# Equipo04_EsquematicoLab05.net
KiCad netlist of a schematic drawn in EAGLE
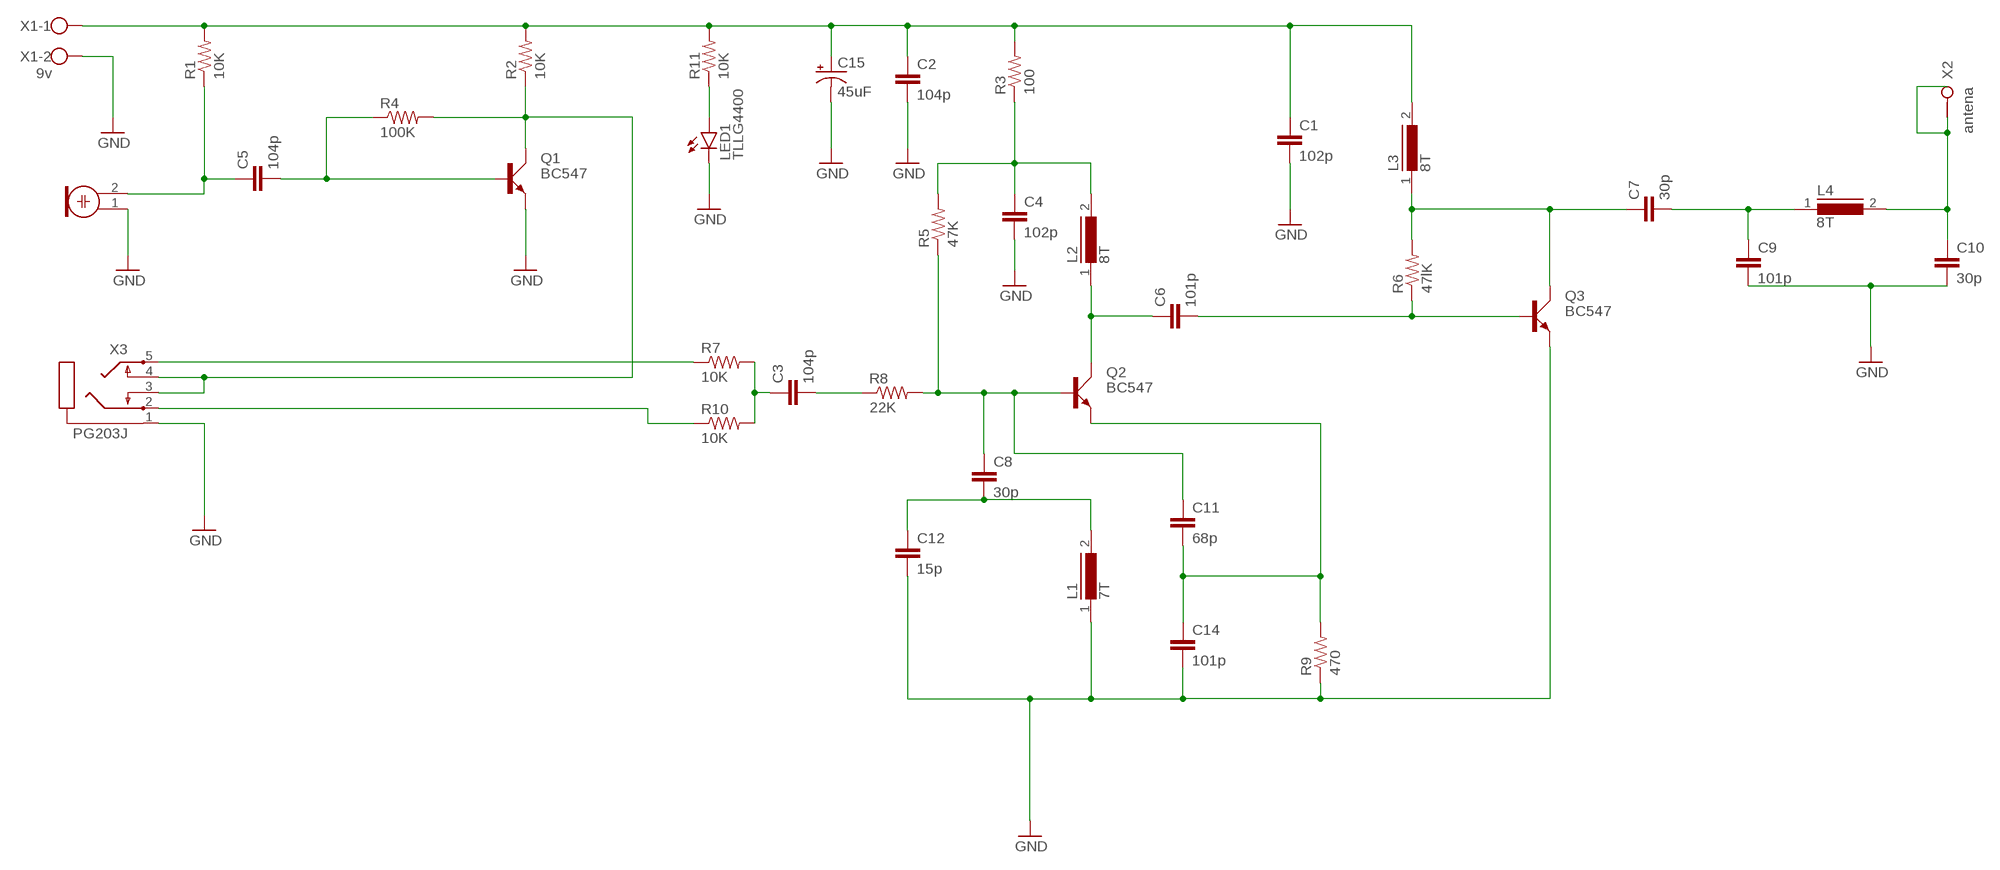
[diagram p0: schematic, sheet 1]

(export (version "E")
  (design (tool "Eeschema 10.0.6"))
  (components
    (comp (ref "C1")
      (value "102p")
      (footprint "eagle-import:C050-024X044")
      (libsource (lib "eagle-import") (part "C-EU050-024X044"))
    )
    (comp (ref "C2")
      (value "104p")
      (footprint "eagle-import:C050-024X044")
      (libsource (lib "eagle-import") (part "C-EU050-024X044"))
    )
    (comp (ref "C3")
      (value "104p")
      (footprint "eagle-import:C050-024X044")
      (libsource (lib "eagle-import") (part "C-EU050-024X044"))
    )
    (comp (ref "C4")
      (value "102p")
      (footprint "eagle-import:C050-024X044")
      (libsource (lib "eagle-import") (part "C-EU050-024X044"))
    )
    (comp (ref "C5")
      (value "104p")
      (footprint "eagle-import:C050-024X044")
      (libsource (lib "eagle-import") (part "C-EU050-024X044"))
    )
    (comp (ref "C6")
      (value "101p")
      (footprint "eagle-import:C050-024X044")
      (libsource (lib "eagle-import") (part "C-EU050-024X044"))
    )
    (comp (ref "C7")
      (value "30p")
      (footprint "eagle-import:C050-024X044")
      (libsource (lib "eagle-import") (part "C-EU050-024X044"))
    )
    (comp (ref "C8")
      (value "30p")
      (footprint "eagle-import:C050-024X044")
      (libsource (lib "eagle-import") (part "C-EU050-024X044"))
    )
    (comp (ref "C9")
      (value "101p")
      (footprint "eagle-import:C050-024X044")
      (libsource (lib "eagle-import") (part "C-EU050-024X044"))
    )
    (comp (ref "C10")
      (value "30p")
      (footprint "eagle-import:C050-024X044")
      (libsource (lib "eagle-import") (part "C-EU050-024X044"))
    )
    (comp (ref "C11")
      (value "68p")
      (footprint "eagle-import:C050-024X044")
      (libsource (lib "eagle-import") (part "C-EU050-024X044"))
    )
    (comp (ref "C12")
      (value "15p")
      (footprint "eagle-import:C050-024X044")
      (libsource (lib "eagle-import") (part "C-EU050-024X044"))
    )
    (comp (ref "C14")
      (value "101p")
      (footprint "eagle-import:C050-024X044")
      (libsource (lib "eagle-import") (part "C-EU050-024X044"))
    )
    (comp (ref "C15")
      (value "45uF")
      (footprint "eagle-import:E2-5")
      (libsource (lib "eagle-import") (part "CPOL-USE2-5"))
    )
    (comp (ref "L1")
      (value "7T")
      (footprint "eagle-import:A26GFC")
      (libsource (lib "eagle-import") (part "A26GFC"))
    )
    (comp (ref "L2")
      (value "8T")
      (footprint "eagle-import:A26GFC")
      (libsource (lib "eagle-import") (part "A26GFC"))
    )
    (comp (ref "L3")
      (value "8T")
      (footprint "eagle-import:A26GFC")
      (libsource (lib "eagle-import") (part "A26GFC"))
    )
    (comp (ref "L4")
      (value "8T")
      (footprint "eagle-import:A26GFC")
      (libsource (lib "eagle-import") (part "A26GFC"))
    )
    (comp (ref "LED1")
      (value "TLLG4400")
      (footprint "eagle-import:LED3MM")
      (fields (field (name "MF") "VISHAY SEMICONDUCTOR"))
      (libsource (lib "eagle-import") (part "TLLG4400"))
    )
    (comp (ref "M1")
      (value "ELECTRET_MICROPHON-WM-62PC/62PK")
      (footprint "eagle-import:WM-62PC_62PK")
      (libsource (lib "eagle-import") (part "ELECTRET_MICROPHON-WM-62PC/62PK"))
    )
    (comp (ref "Q1")
      (value "BC547")
      (footprint "eagle-import:SOT54A")
      (libsource (lib "eagle-import") (part "BC547"))
    )
    (comp (ref "Q2")
      (value "BC547")
      (footprint "eagle-import:SOT54A")
      (libsource (lib "eagle-import") (part "BC547"))
    )
    (comp (ref "Q3")
      (value "BC547")
      (footprint "eagle-import:SOT54A")
      (libsource (lib "eagle-import") (part "BC547"))
    )
    (comp (ref "R1")
      (value "10K")
      (footprint "eagle-import:0309_10")
      (libsource (lib "eagle-import") (part "R-US_0309/10"))
    )
    (comp (ref "R2")
      (value "10K")
      (footprint "eagle-import:0309_10")
      (libsource (lib "eagle-import") (part "R-US_0309/10"))
    )
    (comp (ref "R3")
      (value "100")
      (footprint "eagle-import:0309_10")
      (libsource (lib "eagle-import") (part "R-US_0309/10"))
    )
    (comp (ref "R4")
      (value "100K")
      (footprint "eagle-import:0309_10")
      (libsource (lib "eagle-import") (part "R-US_0309/10"))
    )
    (comp (ref "R5")
      (value "47K")
      (footprint "eagle-import:0309_10")
      (libsource (lib "eagle-import") (part "R-US_0309/10"))
    )
    (comp (ref "R6")
      (value "47lK")
      (footprint "eagle-import:0309_10")
      (libsource (lib "eagle-import") (part "R-US_0309/10"))
    )
    (comp (ref "R7")
      (value "10K")
      (footprint "eagle-import:0309_10")
      (libsource (lib "eagle-import") (part "R-US_0309/10"))
    )
    (comp (ref "R8")
      (value "22K")
      (footprint "eagle-import:0309_10")
      (libsource (lib "eagle-import") (part "R-US_0309/10"))
    )
    (comp (ref "R9")
      (value "470")
      (footprint "eagle-import:0309_10")
      (libsource (lib "eagle-import") (part "R-US_0309/10"))
    )
    (comp (ref "R10")
      (value "10K")
      (footprint "eagle-import:0309_10")
      (libsource (lib "eagle-import") (part "R-US_0309/10"))
    )
    (comp (ref "R11")
      (value "10K")
      (footprint "eagle-import:0309_10")
      (libsource (lib "eagle-import") (part "R-US_0309/10"))
    )
    (comp (ref "X1")
      (value "9v")
      (footprint "eagle-import:W237-102")
      (fields (field (name "MPN") "237-102"))
      (libsource (lib "eagle-import") (part "W237-102"))
    )
    (comp (ref "X2")
      (value "antena")
      (footprint "eagle-import:W236-1")
      (libsource (lib "eagle-import") (part "W236-1"))
    )
    (comp (ref "X3")
      (value "PG203J")
      (footprint "eagle-import:PG203J")
      (libsource (lib "eagle-import") (part "PG203J"))
    )
  )
  (nets
    (net (code "1") (name "GND") (class "Default")
      (node (ref "C1") (pin "2") (pinfunction "2_2") (pintype "passive"))
      (node (ref "C10") (pin "2") (pinfunction "2_2") (pintype "passive"))
      (node (ref "C12") (pin "2") (pinfunction "2_2") (pintype "passive"))
      (node (ref "C14") (pin "2") (pinfunction "2_2") (pintype "passive"))
      (node (ref "C15") (pin "-") (pinfunction "-_-") (pintype "passive"))
      (node (ref "C2") (pin "2") (pinfunction "2_2") (pintype "passive"))
      (node (ref "C4") (pin "2") (pinfunction "2_2") (pintype "passive"))
      (node (ref "C9") (pin "2") (pinfunction "2_2") (pintype "passive"))
      (node (ref "L1") (pin "1") (pinfunction "1_1") (pintype "passive"))
      (node (ref "LED1") (pin "K") (pinfunction "C_K") (pintype "passive"))
      (node (ref "M1") (pin "1") (pinfunction "1_1") (pintype "passive"))
      (node (ref "Q1") (pin "E") (pinfunction "E_E") (pintype "passive"))
      (node (ref "Q3") (pin "E") (pinfunction "E_E") (pintype "passive"))
      (node (ref "R9") (pin "1") (pinfunction "1_1") (pintype "passive"))
      (node (ref "X1") (pin "2") (pinfunction "KL_2") (pintype "passive"))
      (node (ref "X3") (pin "1") (pinfunction "1_1") (pintype "passive"))
    )
    (net (code "2") (name "Net-(C3-Pad1)") (class "Default")
      (node (ref "C3") (pin "1") (pinfunction "1_1") (pintype "passive"))
      (node (ref "R10") (pin "2") (pinfunction "2_2") (pintype "passive"))
      (node (ref "R7") (pin "2") (pinfunction "2_2") (pintype "passive"))
    )
    (net (code "3") (name "Net-(C3-Pad2)") (class "Default")
      (node (ref "C3") (pin "2") (pinfunction "2_2") (pintype "passive"))
      (node (ref "R8") (pin "1") (pinfunction "1_1") (pintype "passive"))
    )
    (net (code "4") (name "Net-(C4-Pad1)") (class "Default")
      (node (ref "C4") (pin "1") (pinfunction "1_1") (pintype "passive"))
      (node (ref "L2") (pin "2") (pinfunction "2_2") (pintype "passive"))
      (node (ref "R3") (pin "1") (pinfunction "1_1") (pintype "passive"))
      (node (ref "R5") (pin "2") (pinfunction "2_2") (pintype "passive"))
    )
    (net (code "5") (name "Net-(C5-Pad1)") (class "Default")
      (node (ref "C5") (pin "1") (pinfunction "1_1") (pintype "passive"))
      (node (ref "M1") (pin "2") (pinfunction "2_2") (pintype "passive"))
      (node (ref "R1") (pin "1") (pinfunction "1_1") (pintype "passive"))
    )
    (net (code "6") (name "Net-(C5-Pad2)") (class "Default")
      (node (ref "C5") (pin "2") (pinfunction "2_2") (pintype "passive"))
      (node (ref "Q1") (pin "B") (pinfunction "B_B") (pintype "passive"))
      (node (ref "R4") (pin "1") (pinfunction "1_1") (pintype "passive"))
    )
    (net (code "7") (name "Net-(C6-Pad1)") (class "Default")
      (node (ref "C6") (pin "1") (pinfunction "1_1") (pintype "passive"))
      (node (ref "L2") (pin "1") (pinfunction "1_1") (pintype "passive"))
      (node (ref "Q2") (pin "C") (pinfunction "C_C") (pintype "passive"))
    )
    (net (code "8") (name "Net-(C6-Pad2)") (class "Default")
      (node (ref "C6") (pin "2") (pinfunction "2_2") (pintype "passive"))
      (node (ref "Q3") (pin "B") (pinfunction "B_B") (pintype "passive"))
      (node (ref "R6") (pin "1") (pinfunction "1_1") (pintype "passive"))
    )
    (net (code "9") (name "Net-(C7-Pad1)") (class "Default")
      (node (ref "C7") (pin "1") (pinfunction "1_1") (pintype "passive"))
      (node (ref "L3") (pin "1") (pinfunction "1_1") (pintype "passive"))
      (node (ref "Q3") (pin "C") (pinfunction "C_C") (pintype "passive"))
      (node (ref "R6") (pin "2") (pinfunction "2_2") (pintype "passive"))
    )
    (net (code "10") (name "Net-(C7-Pad2)") (class "Default")
      (node (ref "C7") (pin "2") (pinfunction "2_2") (pintype "passive"))
      (node (ref "C9") (pin "1") (pinfunction "1_1") (pintype "passive"))
      (node (ref "L4") (pin "1") (pinfunction "1_1") (pintype "passive"))
    )
    (net (code "11") (name "Net-(C11-Pad1)") (class "Default")
      (node (ref "C11") (pin "1") (pinfunction "1_1") (pintype "passive"))
      (node (ref "C8") (pin "1") (pinfunction "1_1") (pintype "passive"))
      (node (ref "Q2") (pin "B") (pinfunction "B_B") (pintype "passive"))
      (node (ref "R5") (pin "1") (pinfunction "1_1") (pintype "passive"))
      (node (ref "R8") (pin "2") (pinfunction "2_2") (pintype "passive"))
    )
    (net (code "12") (name "Net-(C11-Pad2)") (class "Default")
      (node (ref "C11") (pin "2") (pinfunction "2_2") (pintype "passive"))
      (node (ref "C14") (pin "1") (pinfunction "1_1") (pintype "passive"))
      (node (ref "Q2") (pin "E") (pinfunction "E_E") (pintype "passive"))
      (node (ref "R9") (pin "2") (pinfunction "2_2") (pintype "passive"))
    )
    (net (code "13") (name "Net-(C12-Pad1)") (class "Default")
      (node (ref "C12") (pin "1") (pinfunction "1_1") (pintype "passive"))
      (node (ref "C8") (pin "2") (pinfunction "2_2") (pintype "passive"))
      (node (ref "L1") (pin "2") (pinfunction "2_2") (pintype "passive"))
    )
    (net (code "14") (name "Net-(LED1-PadA)") (class "Default")
      (node (ref "LED1") (pin "A") (pinfunction "A_A") (pintype "passive"))
      (node (ref "R11") (pin "1") (pinfunction "1_1") (pintype "passive"))
    )
    (net (code "15") (name "Net-(Q1-PadC)") (class "Default")
      (node (ref "Q1") (pin "C") (pinfunction "C_C") (pintype "passive"))
      (node (ref "R2") (pin "1") (pinfunction "1_1") (pintype "passive"))
      (node (ref "R4") (pin "2") (pinfunction "2_2") (pintype "passive"))
      (node (ref "X3") (pin "3") (pinfunction "3_3") (pintype "passive"))
      (node (ref "X3") (pin "4") (pinfunction "4_4") (pintype "passive"))
    )
    (net (code "16") (name "Net-(R7-Pad1)") (class "Default")
      (node (ref "R7") (pin "1") (pinfunction "1_1") (pintype "passive"))
      (node (ref "X3") (pin "5") (pinfunction "5_5") (pintype "passive"))
    )
    (net (code "17") (name "Net-(R10-Pad1)") (class "Default")
      (node (ref "R10") (pin "1") (pinfunction "1_1") (pintype "passive"))
      (node (ref "X3") (pin "2") (pinfunction "2_2") (pintype "passive"))
    )
    (net (code "18") (name "Net-(X1A-KL)") (class "Default")
      (node (ref "C1") (pin "1") (pinfunction "1_1") (pintype "passive"))
      (node (ref "C15") (pin "+") (pinfunction "+_+") (pintype "passive"))
      (node (ref "C2") (pin "1") (pinfunction "1_1") (pintype "passive"))
      (node (ref "L3") (pin "2") (pinfunction "2_2") (pintype "passive"))
      (node (ref "R1") (pin "2") (pinfunction "2_2") (pintype "passive"))
      (node (ref "R11") (pin "2") (pinfunction "2_2") (pintype "passive"))
      (node (ref "R2") (pin "2") (pinfunction "2_2") (pintype "passive"))
      (node (ref "R3") (pin "2") (pinfunction "2_2") (pintype "passive"))
      (node (ref "X1") (pin "1") (pinfunction "KL_1") (pintype "passive"))
    )
    (net (code "19") (name "Net-(X2-KL1)") (class "Default")
      (node (ref "C10") (pin "1") (pinfunction "1_1") (pintype "passive"))
      (node (ref "L4") (pin "2") (pinfunction "2_2") (pintype "passive"))
      (node (ref "X2") (pin "1") (pinfunction "KL1_1") (pintype "passive"))
    )
    (net (code "20") (name "unconnected-(X2-KL2-Pad2)") (class "Default")
      (node (ref "X2") (pin "2") (pinfunction "KL2_2") (pintype "passive"))
    )
  )
)
